# completefilter.net
KiCad netlist of a schematic drawn in EAGLE
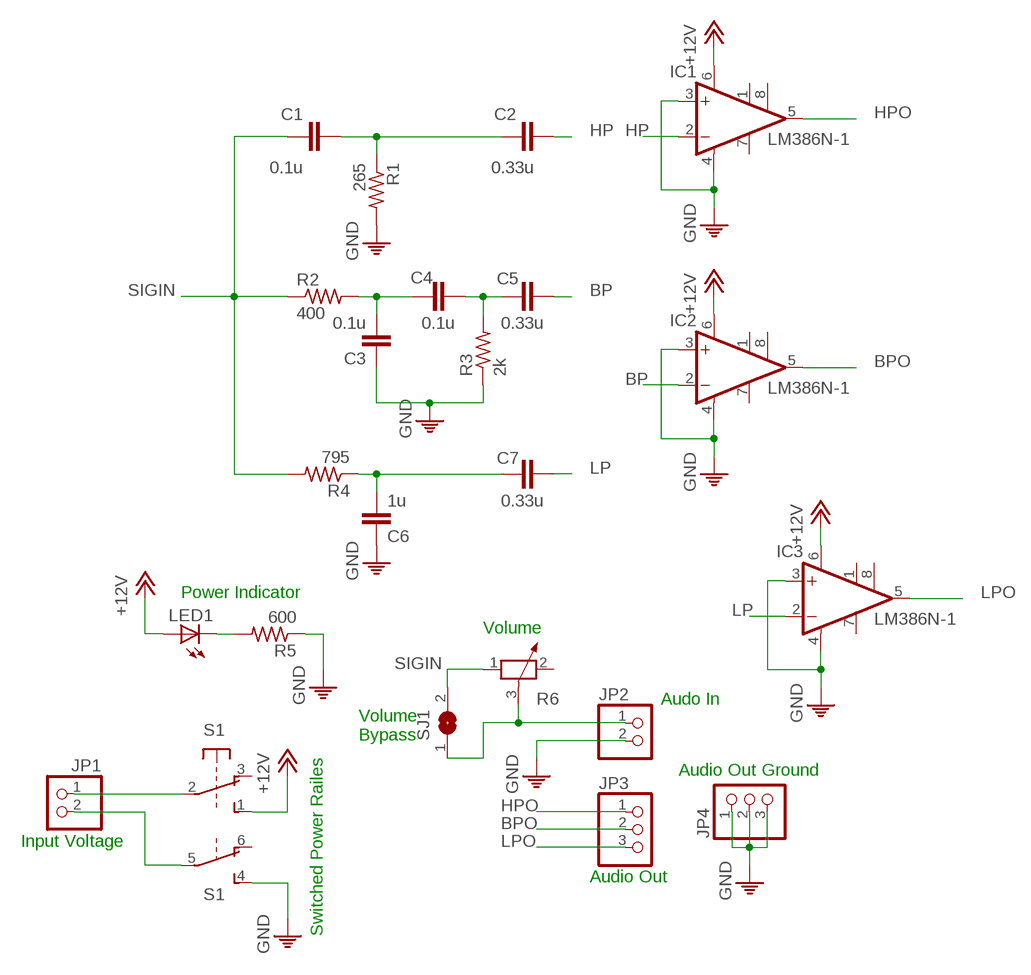
[diagram p0: schematic, sheet 1]

(export (version "E")
  (design (tool "Eeschema 10.0.6"))
  (components
    (comp (ref "C1")
      (value "0.1u")
      (footprint "eagle-import:C1206")
      (libsource (lib "eagle-import") (part "C-EUC1206"))
    )
    (comp (ref "C2")
      (value "0.33u")
      (footprint "eagle-import:C1206")
      (libsource (lib "eagle-import") (part "C-EUC1206"))
    )
    (comp (ref "C3")
      (value "0.1u")
      (footprint "eagle-import:C1206")
      (libsource (lib "eagle-import") (part "C-EUC1206"))
    )
    (comp (ref "C4")
      (value "0.1u")
      (footprint "eagle-import:C1206")
      (libsource (lib "eagle-import") (part "C-EUC1206"))
    )
    (comp (ref "C5")
      (value "0.33u")
      (footprint "eagle-import:C1206")
      (libsource (lib "eagle-import") (part "C-EUC1206"))
    )
    (comp (ref "C6")
      (value "1u")
      (footprint "eagle-import:C1206")
      (libsource (lib "eagle-import") (part "C-EUC1206"))
    )
    (comp (ref "C7")
      (value "0.33u")
      (footprint "eagle-import:C1206")
      (libsource (lib "eagle-import") (part "C-EUC1206"))
    )
    (comp (ref "IC1")
      (value "LM386N-1")
      (footprint "eagle-import:DIL08")
      (libsource (lib "eagle-import") (part "LM386?-N1"))
    )
    (comp (ref "IC2")
      (value "LM386N-1")
      (footprint "eagle-import:DIL08")
      (libsource (lib "eagle-import") (part "LM386?-N1"))
    )
    (comp (ref "IC3")
      (value "LM386N-1")
      (footprint "eagle-import:DIL08")
      (libsource (lib "eagle-import") (part "LM386?-N1"))
    )
    (comp (ref "JP1")
      (value "PINHD-1X2")
      (footprint "eagle-import:1X02")
      (libsource (lib "eagle-import") (part "PINHD-1X2"))
    )
    (comp (ref "JP2")
      (value "PINHD-1X2")
      (footprint "eagle-import:1X02")
      (libsource (lib "eagle-import") (part "PINHD-1X2"))
    )
    (comp (ref "JP3")
      (value "PINHD-1X3")
      (footprint "eagle-import:1X03")
      (libsource (lib "eagle-import") (part "PINHD-1X3"))
    )
    (comp (ref "JP4")
      (value "PINHD-1X3")
      (footprint "eagle-import:1X03")
      (libsource (lib "eagle-import") (part "PINHD-1X3"))
    )
    (comp (ref "LED1")
      (value "LED3MM")
      (footprint "eagle-import:LED3MM")
      (libsource (lib "eagle-import") (part "LED3MM"))
    )
    (comp (ref "R1")
      (value "265")
      (footprint "eagle-import:R1206")
      (libsource (lib "eagle-import") (part "R-US_R1206"))
    )
    (comp (ref "R2")
      (value "400")
      (footprint "eagle-import:R1206")
      (libsource (lib "eagle-import") (part "R-US_R1206"))
    )
    (comp (ref "R3")
      (value "2k")
      (footprint "eagle-import:R1206")
      (libsource (lib "eagle-import") (part "R-US_R1206"))
    )
    (comp (ref "R4")
      (value "795")
      (footprint "eagle-import:R1206")
      (libsource (lib "eagle-import") (part "R-US_R1206"))
    )
    (comp (ref "R5")
      (value "600")
      (footprint "eagle-import:R1206")
      (libsource (lib "eagle-import") (part "R-US_R1206"))
    )
    (comp (ref "R6")
      (value "POTENTIOMETER_PT-10")
      (footprint "eagle-import:PT-10")
      (libsource (lib "eagle-import") (part "POTENTIOMETER_PT-10"))
    )
    (comp (ref "S1")
      (value "9450-2")
      (footprint "eagle-import:9450-2")
      (libsource (lib "eagle-import") (part "9450-2"))
    )
    (comp (ref "SJ1")
      (value "SJW")
      (footprint "eagle-import:SJW")
      (libsource (lib "eagle-import") (part "SJW"))
    )
  )
  (nets
    (net (code "1") (name "+12V") (class "Default")
      (node (ref "IC1") (pin "6") (pinfunction "VS_6") (pintype "power_in"))
      (node (ref "IC2") (pin "6") (pinfunction "VS_6") (pintype "power_in"))
      (node (ref "IC3") (pin "6") (pinfunction "VS_6") (pintype "power_in"))
      (node (ref "LED1") (pin "A") (pinfunction "A_A") (pintype "passive"))
      (node (ref "S1") (pin "1") (pinfunction "S_1") (pintype "passive"))
    )
    (net (code "2") (name "/BP") (class "Default")
      (node (ref "C5") (pin "1") (pinfunction "1_1") (pintype "passive"))
      (node (ref "IC2") (pin "2") (pinfunction "-IN_2") (pintype "input"))
    )
    (net (code "3") (name "/BPO") (class "Default")
      (node (ref "IC2") (pin "5") (pinfunction "OUT_5") (pintype "output"))
      (node (ref "JP3") (pin "2") (pinfunction "2_2") (pintype "passive"))
    )
    (net (code "4") (name "/HP") (class "Default")
      (node (ref "C2") (pin "2") (pinfunction "2_2") (pintype "passive"))
      (node (ref "IC1") (pin "2") (pinfunction "-IN_2") (pintype "input"))
    )
    (net (code "5") (name "/HPO") (class "Default")
      (node (ref "IC1") (pin "5") (pinfunction "OUT_5") (pintype "output"))
      (node (ref "JP3") (pin "1") (pinfunction "1_1") (pintype "passive"))
    )
    (net (code "6") (name "/LP") (class "Default")
      (node (ref "C7") (pin "1") (pinfunction "1_1") (pintype "passive"))
      (node (ref "IC3") (pin "2") (pinfunction "-IN_2") (pintype "input"))
    )
    (net (code "7") (name "/LPO") (class "Default")
      (node (ref "IC3") (pin "5") (pinfunction "OUT_5") (pintype "output"))
      (node (ref "JP3") (pin "3") (pinfunction "3_3") (pintype "passive"))
    )
    (net (code "8") (name "/SIGIN") (class "Default")
      (node (ref "C1") (pin "1") (pinfunction "1_1") (pintype "passive"))
      (node (ref "R2") (pin "1") (pinfunction "1_1") (pintype "passive"))
      (node (ref "R4") (pin "2") (pinfunction "2_2") (pintype "passive"))
      (node (ref "R6") (pin "1") (pinfunction "1_1") (pintype "passive"))
      (node (ref "SJ1") (pin "2") (pinfunction "2_2") (pintype "passive"))
    )
    (net (code "9") (name "GND") (class "Default")
      (node (ref "C3") (pin "1") (pinfunction "1_1") (pintype "passive"))
      (node (ref "C6") (pin "1") (pinfunction "1_1") (pintype "passive"))
      (node (ref "IC1") (pin "3") (pinfunction "+IN_3") (pintype "input"))
      (node (ref "IC1") (pin "4") (pinfunction "GND_4") (pintype "power_in"))
      (node (ref "IC2") (pin "3") (pinfunction "+IN_3") (pintype "input"))
      (node (ref "IC2") (pin "4") (pinfunction "GND_4") (pintype "power_in"))
      (node (ref "IC3") (pin "3") (pinfunction "+IN_3") (pintype "input"))
      (node (ref "IC3") (pin "4") (pinfunction "GND_4") (pintype "power_in"))
      (node (ref "JP2") (pin "2") (pinfunction "2_2") (pintype "passive"))
      (node (ref "JP4") (pin "1") (pinfunction "1_1") (pintype "passive"))
      (node (ref "JP4") (pin "2") (pinfunction "2_2") (pintype "passive"))
      (node (ref "JP4") (pin "3") (pinfunction "3_3") (pintype "passive"))
      (node (ref "R1") (pin "2") (pinfunction "2_2") (pintype "passive"))
      (node (ref "R3") (pin "1") (pinfunction "1_1") (pintype "passive"))
      (node (ref "R5") (pin "1") (pinfunction "1_1") (pintype "passive"))
      (node (ref "S1") (pin "4") (pinfunction "S_4") (pintype "passive"))
    )
    (net (code "10") (name "Net-(C1-Pad2)") (class "Default")
      (node (ref "C1") (pin "2") (pinfunction "2_2") (pintype "passive"))
      (node (ref "C2") (pin "1") (pinfunction "1_1") (pintype "passive"))
      (node (ref "R1") (pin "1") (pinfunction "1_1") (pintype "passive"))
    )
    (net (code "11") (name "Net-(C3-Pad2)") (class "Default")
      (node (ref "C3") (pin "2") (pinfunction "2_2") (pintype "passive"))
      (node (ref "C4") (pin "2") (pinfunction "2_2") (pintype "passive"))
      (node (ref "R2") (pin "2") (pinfunction "2_2") (pintype "passive"))
    )
    (net (code "12") (name "Net-(C4-Pad1)") (class "Default")
      (node (ref "C4") (pin "1") (pinfunction "1_1") (pintype "passive"))
      (node (ref "C5") (pin "2") (pinfunction "2_2") (pintype "passive"))
      (node (ref "R3") (pin "2") (pinfunction "2_2") (pintype "passive"))
    )
    (net (code "13") (name "Net-(C6-Pad2)") (class "Default")
      (node (ref "C6") (pin "2") (pinfunction "2_2") (pintype "passive"))
      (node (ref "C7") (pin "2") (pinfunction "2_2") (pintype "passive"))
      (node (ref "R4") (pin "1") (pinfunction "1_1") (pintype "passive"))
    )
    (net (code "14") (name "Net-(JP2-Pad1)") (class "Default")
      (node (ref "JP2") (pin "1") (pinfunction "1_1") (pintype "passive"))
      (node (ref "R6") (pin "3") (pinfunction "3_3") (pintype "passive"))
      (node (ref "SJ1") (pin "1") (pinfunction "1_1") (pintype "passive"))
    )
    (net (code "15") (name "Net-(LED1-C)") (class "Default")
      (node (ref "LED1") (pin "K") (pinfunction "C_K") (pintype "passive"))
      (node (ref "R5") (pin "2") (pinfunction "2_2") (pintype "passive"))
    )
    (net (code "16") (name "Net-(S1A-P)") (class "Default")
      (node (ref "JP1") (pin "1") (pinfunction "1_1") (pintype "passive"))
      (node (ref "S1") (pin "2") (pinfunction "P_2") (pintype "passive"))
    )
    (net (code "17") (name "Net-(S1B-P)") (class "Default")
      (node (ref "JP1") (pin "2") (pinfunction "2_2") (pintype "passive"))
      (node (ref "S1") (pin "5") (pinfunction "P_5") (pintype "passive"))
    )
    (net (code "18") (name "unconnected-(IC1-BYPASS-Pad7)") (class "Default")
      (node (ref "IC1") (pin "7") (pinfunction "BYPASS_7") (pintype "passive"))
    )
    (net (code "19") (name "unconnected-(IC1-GAIN-Pad1)") (class "Default")
      (node (ref "IC1") (pin "1") (pinfunction "GAIN_1") (pintype "passive"))
    )
    (net (code "20") (name "unconnected-(IC1-GAIN-Pad8)") (class "Default")
      (node (ref "IC1") (pin "8") (pinfunction "GAIN_8") (pintype "passive"))
    )
    (net (code "21") (name "unconnected-(IC2-BYPASS-Pad7)") (class "Default")
      (node (ref "IC2") (pin "7") (pinfunction "BYPASS_7") (pintype "passive"))
    )
    (net (code "22") (name "unconnected-(IC2-GAIN-Pad1)") (class "Default")
      (node (ref "IC2") (pin "1") (pinfunction "GAIN_1") (pintype "passive"))
    )
    (net (code "23") (name "unconnected-(IC2-GAIN-Pad8)") (class "Default")
      (node (ref "IC2") (pin "8") (pinfunction "GAIN_8") (pintype "passive"))
    )
    (net (code "24") (name "unconnected-(IC3-BYPASS-Pad7)") (class "Default")
      (node (ref "IC3") (pin "7") (pinfunction "BYPASS_7") (pintype "passive"))
    )
    (net (code "25") (name "unconnected-(IC3-GAIN-Pad1)") (class "Default")
      (node (ref "IC3") (pin "1") (pinfunction "GAIN_1") (pintype "passive"))
    )
    (net (code "26") (name "unconnected-(IC3-GAIN-Pad8)") (class "Default")
      (node (ref "IC3") (pin "8") (pinfunction "GAIN_8") (pintype "passive"))
    )
    (net (code "27") (name "unconnected-(R6-Pad2)") (class "Default")
      (node (ref "R6") (pin "2") (pinfunction "2_2") (pintype "passive"))
    )
    (net (code "28") (name "unconnected-(S1A-O-Pad3)") (class "Default")
      (node (ref "S1") (pin "3") (pinfunction "O_3") (pintype "passive"))
    )
    (net (code "29") (name "unconnected-(S1B-O-Pad6)") (class "Default")
      (node (ref "S1") (pin "6") (pinfunction "O_6") (pintype "passive"))
    )
  )
)
